# SCH_Just-random_2026-04-02_2.net
KiCad netlist of a schematic drawn in EasyEDA
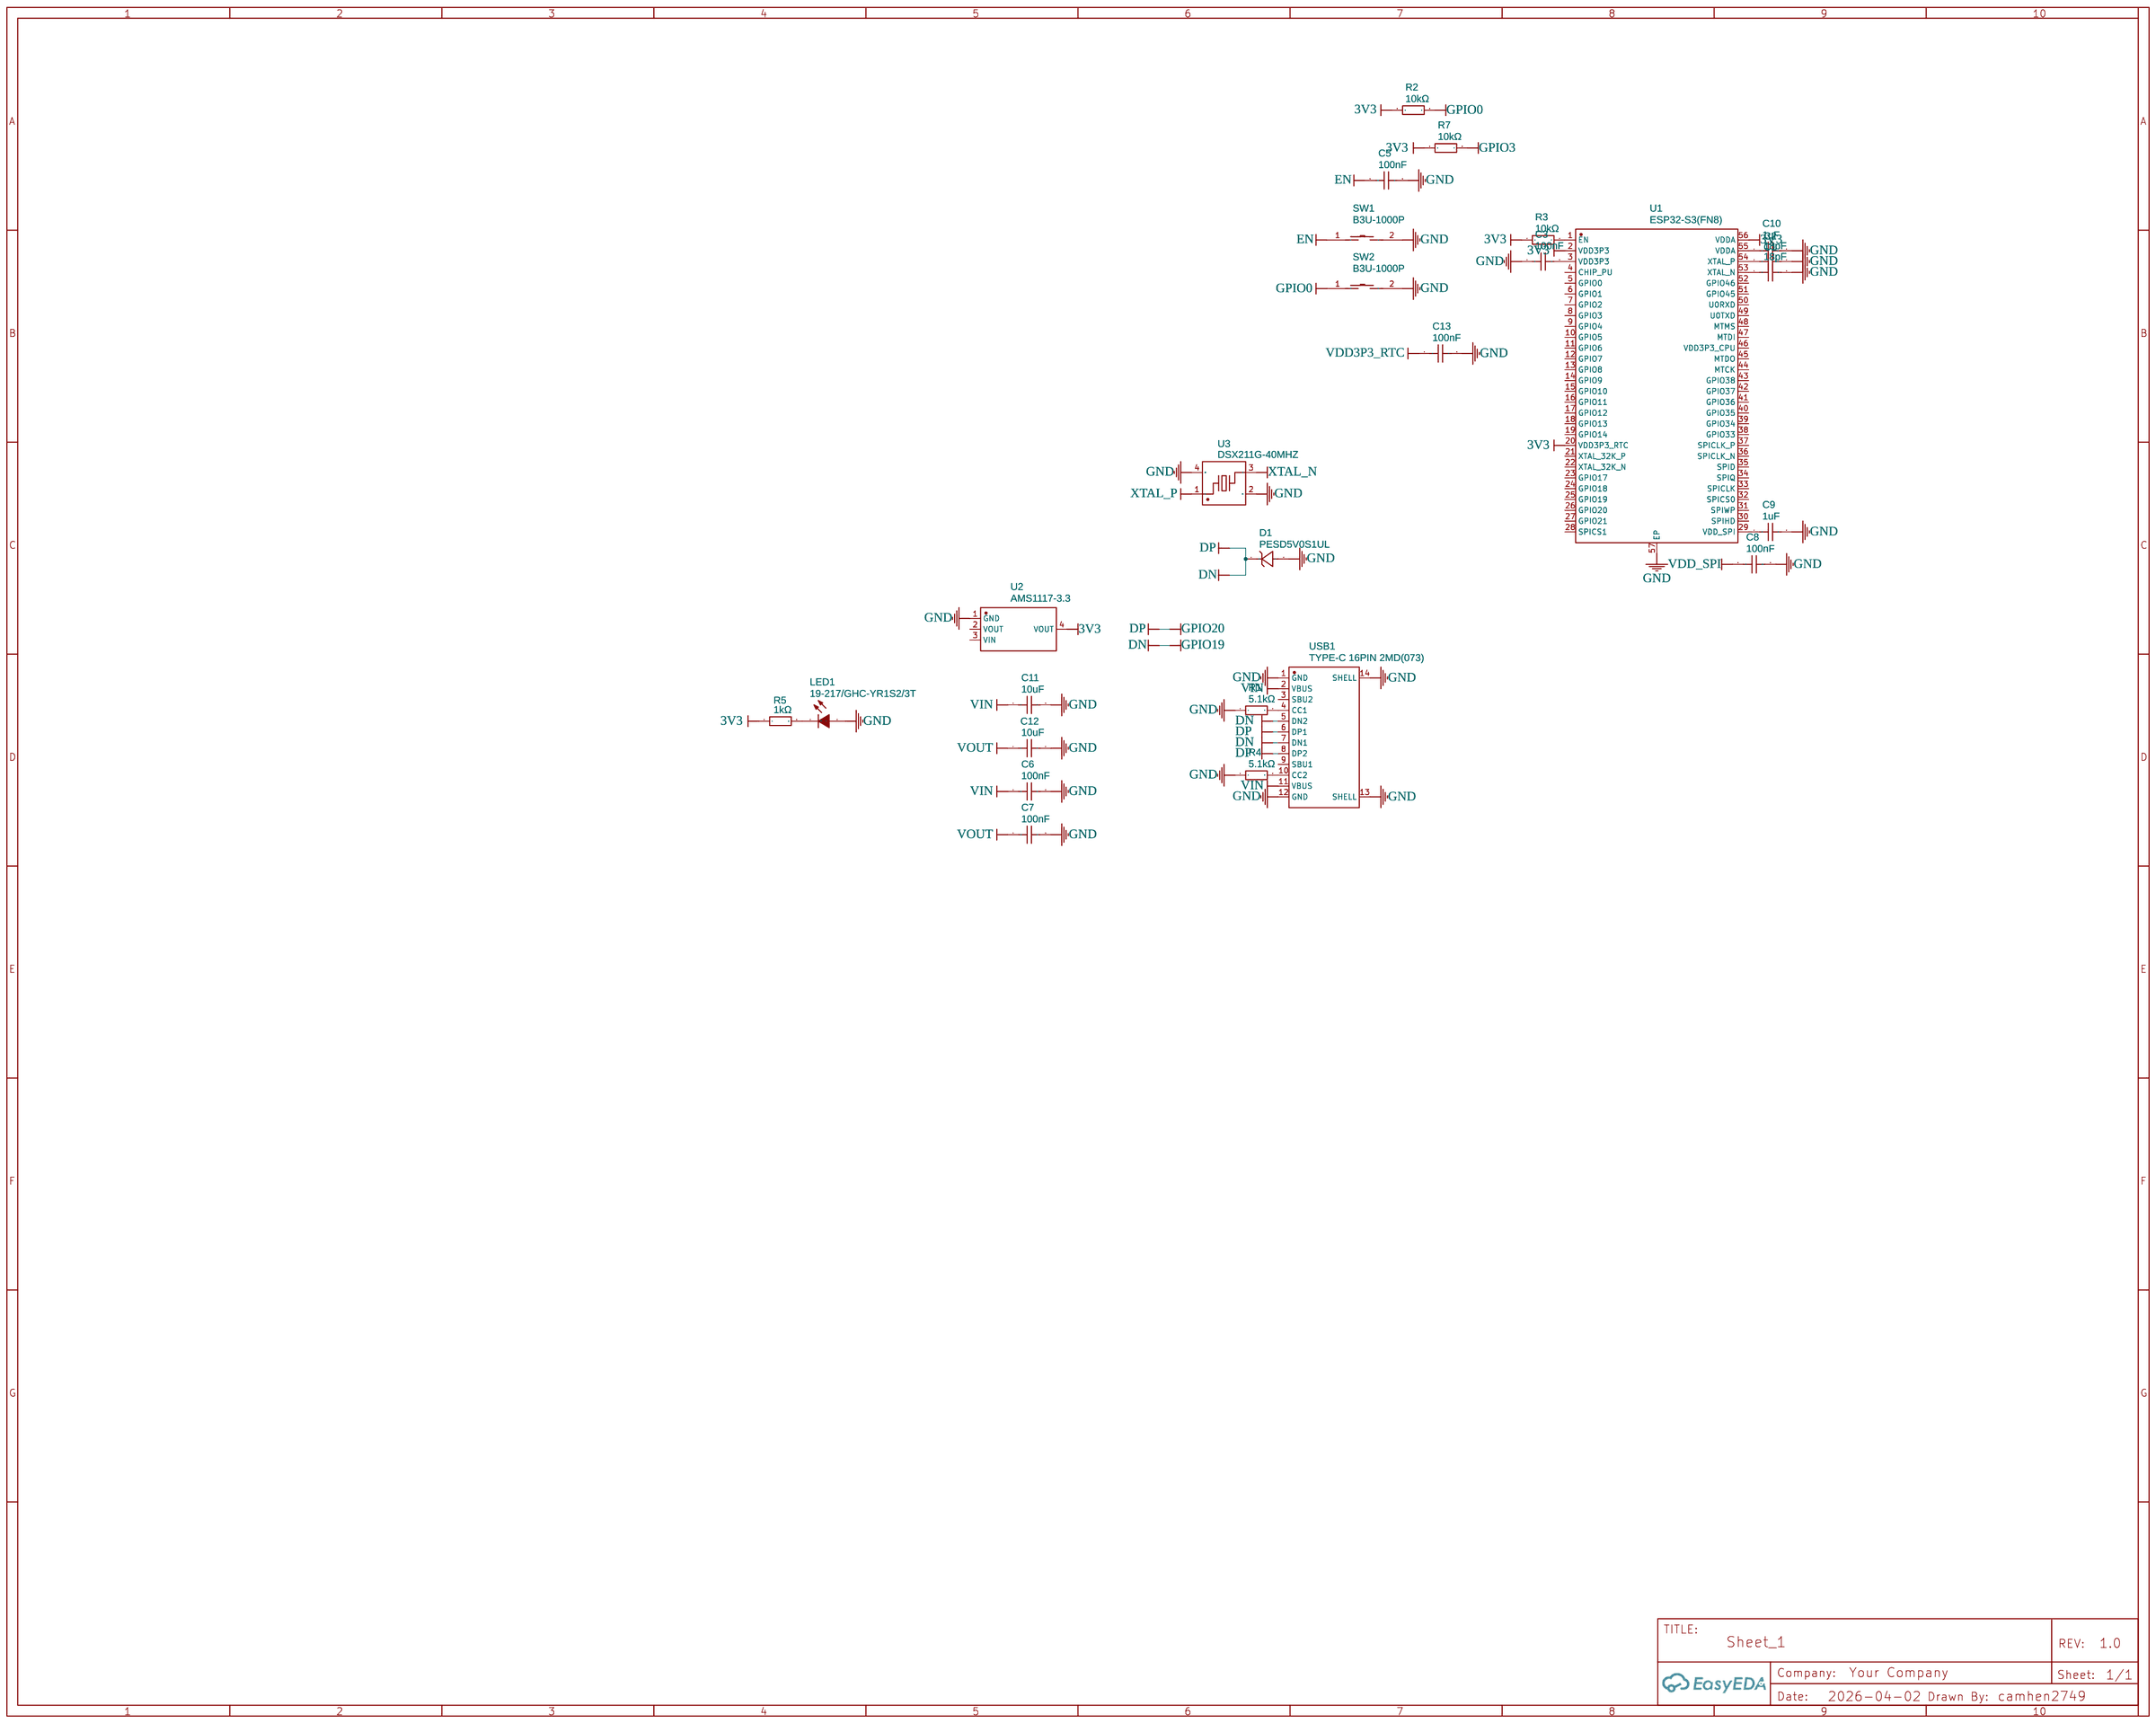
[diagram p0: schematic sheet]

(export (version "E")
  (design (tool "Eeschema 10.0.6"))
  (components
    (comp (ref "C1")
      (value "18pF")
      (fields
        (field (name "Manufacturer Part") "CL05C180JB5NNNC")
        (field (name "Manufacturer") "SAMSUNG(三星)")
      )
      (libsource (lib "") (part "CL05C180JB5NNNC"))
    )
    (comp (ref "C2")
      (value "18pF")
      (fields
        (field (name "Manufacturer Part") "CL05C180JB5NNNC")
        (field (name "Manufacturer") "SAMSUNG(三星)")
      )
      (libsource (lib "") (part "CL05C180JB5NNNC_1"))
    )
    (comp (ref "C3")
      (value "100nF")
      (fields
        (field (name "Manufacturer Part") "CL05B104KO5NNNC")
        (field (name "Manufacturer") "SAMSUNG(三星)")
      )
      (libsource (lib "") (part "CL05B104KO5NNNC"))
    )
    (comp (ref "C5")
      (value "100nF")
      (fields
        (field (name "Manufacturer Part") "CL05B104KO5NNNC")
        (field (name "Manufacturer") "SAMSUNG(三星)")
      )
      (libsource (lib "") (part "CL05B104KO5NNNC"))
    )
    (comp (ref "C6")
      (value "100nF")
      (fields
        (field (name "Manufacturer Part") "CL05B104KO5NNNC")
        (field (name "Manufacturer") "SAMSUNG(三星)")
      )
      (libsource (lib "") (part "CL05B104KO5NNNC"))
    )
    (comp (ref "C7")
      (value "100nF")
      (fields
        (field (name "Manufacturer Part") "CL05B104KO5NNNC")
        (field (name "Manufacturer") "SAMSUNG(三星)")
      )
      (libsource (lib "") (part "CL05B104KO5NNNC"))
    )
    (comp (ref "C8")
      (value "100nF")
      (fields
        (field (name "Manufacturer Part") "CL05B104KO5NNNC")
        (field (name "Manufacturer") "SAMSUNG(三星)")
      )
      (libsource (lib "") (part "CL05B104KO5NNNC"))
    )
    (comp (ref "C9")
      (value "1uF")
      (fields
        (field (name "Manufacturer Part") "CL05A105KA5NQNC")
        (field (name "Manufacturer") "SAMSUNG(三星)")
      )
      (libsource (lib "") (part "CL05A105KA5NQNC"))
    )
    (comp (ref "C10")
      (value "1uF")
      (fields
        (field (name "Manufacturer Part") "CL05A105KA5NQNC")
        (field (name "Manufacturer") "SAMSUNG(三星)")
      )
      (libsource (lib "") (part "CL05A105KA5NQNC"))
    )
    (comp (ref "C11")
      (value "10uF")
      (fields
        (field (name "Manufacturer Part") "CL21A106KAYNNNE")
        (field (name "Manufacturer") "SAMSUNG(三星)")
      )
      (libsource (lib "") (part "CL21A106KAYNNNE"))
    )
    (comp (ref "C12")
      (value "10uF")
      (fields
        (field (name "Manufacturer Part") "CL21A106KAYNNNE")
        (field (name "Manufacturer") "SAMSUNG(三星)")
      )
      (libsource (lib "") (part "CL21A106KAYNNNE"))
    )
    (comp (ref "C13")
      (value "100nF")
      (fields
        (field (name "Manufacturer Part") "CL05B104KO5NNNC")
        (field (name "Manufacturer") "SAMSUNG(三星)")
      )
      (libsource (lib "") (part "CL05B104KO5NNNC"))
    )
    (comp (ref "D1")
      (value "PESD5V0S1UL")
      (fields (field (name "Manufacturer") "TECH PUBLIC(台舟)"))
      (libsource (lib "") (part "PESD5V0S1UL"))
    )
    (comp (ref "LED1")
      (value "19-217/GHC-YR1S2/3T")
      (fields (field (name "Manufacturer") "EVERLIGHT(亿光)"))
      (libsource (lib "") (part "19-217/GHC-YR1S2/3T"))
    )
    (comp (ref "R1")
      (value "5.1kΩ")
      (fields (field (name "Manufacturer Part") "RC0402FR-075K1L") (field (name "Manufacturer") "YAGEO(国巨)"))
      (libsource (lib "") (part "RC0402FR-075K1L"))
    )
    (comp (ref "R2")
      (value "10kΩ")
      (fields (field (name "Manufacturer Part") "RC0402FR-0710KL") (field (name "Manufacturer") "YAGEO(国巨)"))
      (libsource (lib "") (part "RC0402FR-0710KL"))
    )
    (comp (ref "R3")
      (value "10kΩ")
      (fields (field (name "Manufacturer Part") "RC0402FR-0710KL") (field (name "Manufacturer") "YAGEO(国巨)"))
      (libsource (lib "") (part "RC0402FR-0710KL"))
    )
    (comp (ref "R4")
      (value "5.1kΩ")
      (fields (field (name "Manufacturer Part") "RC0402FR-075K1L") (field (name "Manufacturer") "YAGEO(国巨)"))
      (libsource (lib "") (part "RC0402FR-075K1L"))
    )
    (comp (ref "R5")
      (value "1kΩ")
      (fields (field (name "Manufacturer Part") "RC0402FR-071KL") (field (name "Manufacturer") "YAGEO(国巨)"))
      (libsource (lib "") (part "RC0402FR-071KL"))
    )
    (comp (ref "R7")
      (value "10kΩ")
      (fields (field (name "Manufacturer Part") "RC0402FR-0710KL") (field (name "Manufacturer") "YAGEO(国巨)"))
      (libsource (lib "") (part "RC0402FR-0710KL"))
    )
    (comp (ref "SW1")
      (value "B3U-1000P")
      (fields (field (name "Manufacturer") "OMRON(欧姆龙)"))
      (libsource (lib "") (part "B3U-1000P"))
    )
    (comp (ref "SW2")
      (value "B3U-1000P")
      (fields (field (name "Manufacturer") "OMRON(欧姆龙)"))
      (libsource (lib "") (part "B3U-1000P"))
    )
    (comp (ref "U1")
      (value "ESP32-S3(FN8)")
      (fields (field (name "Manufacturer Part") "ESP32-S3FN8") (field (name "Manufacturer") "ESPRESSIF(乐鑫)"))
      (libsource (lib "") (part "ESP32-S3(FN8)"))
    )
    (comp (ref "U2")
      (value "AMS1117-3.3")
      (fields (field (name "Manufacturer") "AMS"))
      (libsource (lib "") (part "AMS1117-3.3"))
    )
    (comp (ref "U3")
      (value "DSX211G-40MHZ")
      (fields (field (name "Manufacturer Part") "DSX211G-40MHz"))
      (libsource (lib "") (part "DSX211G-40MHZ"))
    )
    (comp (ref "USB1")
      (value "TYPE-C 16PIN 2MD(073)")
      (fields (field (name "Manufacturer") "SHOU HAN(首韩)"))
      (libsource (lib "") (part "TYPE-C 16PIN 2MD(073)"))
    )
  )
  (nets
    (net (code "1") (name "3V3") (class "Default")
      (node (ref "R2") (pin "1") (pinfunction "1_1") (pintype "input"))
      (node (ref "R3") (pin "1") (pinfunction "1_1") (pintype "input"))
      (node (ref "R5") (pin "1") (pinfunction "1_1") (pintype "input"))
      (node (ref "R7") (pin "1") (pinfunction "1_1") (pintype "input"))
      (node (ref "U1") (pin "2") (pinfunction "VDD3P3_2") (pintype "unspecified"))
      (node (ref "U1") (pin "20") (pinfunction "VDD3P3_RTC_20") (pintype "unspecified"))
      (node (ref "U1") (pin "56") (pinfunction "VDDA_56") (pintype "unspecified"))
      (node (ref "U2") (pin "4") (pinfunction "VOUT_4") (pintype "unspecified"))
    )
    (net (code "2") (name "DN") (class "Default")
      (node (ref "D1") (pin "1") (pinfunction "C_1") (pintype "unspecified"))
      (node (ref "USB1") (pin "5") (pinfunction "DN2_5") (pintype "unspecified"))
      (node (ref "USB1") (pin "6") (pinfunction "DP1_6") (pintype "unspecified"))
      (node (ref "USB1") (pin "7") (pinfunction "DN1_7") (pintype "unspecified"))
      (node (ref "USB1") (pin "8") (pinfunction "DP2_8") (pintype "unspecified"))
    )
    (net (code "3") (name "EN") (class "Default")
      (node (ref "C5") (pin "1") (pinfunction "1_1") (pintype "unspecified"))
      (node (ref "SW1") (pin "1") (pinfunction "1_1") (pintype "unspecified"))
    )
    (net (code "4") (name "GND") (class "Default")
      (node (ref "C1") (pin "2") (pinfunction "2_2") (pintype "unspecified"))
      (node (ref "C10") (pin "2") (pinfunction "2_2") (pintype "unspecified"))
      (node (ref "C11") (pin "2") (pinfunction "2_2") (pintype "unspecified"))
      (node (ref "C12") (pin "2") (pinfunction "2_2") (pintype "unspecified"))
      (node (ref "C13") (pin "2") (pinfunction "2_2") (pintype "unspecified"))
      (node (ref "C2") (pin "1") (pinfunction "1_1") (pintype "unspecified"))
      (node (ref "C3") (pin "1") (pinfunction "1_1") (pintype "unspecified"))
      (node (ref "C5") (pin "2") (pinfunction "2_2") (pintype "unspecified"))
      (node (ref "C6") (pin "2") (pinfunction "2_2") (pintype "unspecified"))
      (node (ref "C7") (pin "2") (pinfunction "2_2") (pintype "unspecified"))
      (node (ref "C8") (pin "2") (pinfunction "2_2") (pintype "unspecified"))
      (node (ref "C9") (pin "2") (pinfunction "2_2") (pintype "unspecified"))
      (node (ref "D1") (pin "2") (pinfunction "A_2") (pintype "unspecified"))
      (node (ref "LED1") (pin "2") (pinfunction "A_2") (pintype "input"))
      (node (ref "R1") (pin "1") (pinfunction "1_1") (pintype "input"))
      (node (ref "R4") (pin "1") (pinfunction "1_1") (pintype "input"))
      (node (ref "SW1") (pin "2") (pinfunction "2_2") (pintype "unspecified"))
      (node (ref "SW2") (pin "2") (pinfunction "2_2") (pintype "unspecified"))
      (node (ref "U1") (pin "57") (pinfunction "EP_57") (pintype "unspecified"))
      (node (ref "U2") (pin "1") (pinfunction "GND_1") (pintype "unspecified"))
      (node (ref "U3") (pin "2") (pinfunction "GND/NC_2") (pintype "input"))
      (node (ref "U3") (pin "4") (pinfunction "GND/NC_4") (pintype "input"))
      (node (ref "USB1") (pin "1") (pinfunction "GND_1") (pintype "unspecified"))
      (node (ref "USB1") (pin "12") (pinfunction "GND_12") (pintype "unspecified"))
      (node (ref "USB1") (pin "13") (pinfunction "SHELL_13") (pintype "unspecified"))
      (node (ref "USB1") (pin "14") (pinfunction "SHELL_14") (pintype "unspecified"))
    )
    (net (code "5") (name "GPIO0") (class "Default")
      (node (ref "R2") (pin "2") (pinfunction "2_2") (pintype "input"))
      (node (ref "SW2") (pin "1") (pinfunction "1_1") (pintype "unspecified"))
    )
    (net (code "6") (name "GPIO3") (class "Default")
      (node (ref "R7") (pin "2") (pinfunction "2_2") (pintype "input"))
    )
    (net (code "7") (name "Net-(C3-Pad2)") (class "Default")
      (node (ref "C3") (pin "2") (pinfunction "2_2") (pintype "unspecified"))
      (node (ref "U1") (pin "3") (pinfunction "VDD3P3_3") (pintype "unspecified"))
    )
    (net (code "8") (name "Net-(C10-Pad1)") (class "Default")
      (node (ref "C10") (pin "1") (pinfunction "1_1") (pintype "unspecified"))
      (node (ref "U1") (pin "55") (pinfunction "VDDA_55") (pintype "unspecified"))
    )
    (net (code "9") (name "Net-(LED1-C)") (class "Default")
      (node (ref "LED1") (pin "1") (pinfunction "C_1") (pintype "input"))
      (node (ref "R5") (pin "2") (pinfunction "2_2") (pintype "input"))
    )
    (net (code "10") (name "Net-(U1-EN)") (class "Default")
      (node (ref "R3") (pin "2") (pinfunction "2_2") (pintype "input"))
      (node (ref "U1") (pin "1") (pinfunction "EN_1") (pintype "unspecified"))
    )
    (net (code "11") (name "Net-(U1-VDD_SPI)") (class "Default")
      (node (ref "C9") (pin "1") (pinfunction "1_1") (pintype "unspecified"))
      (node (ref "U1") (pin "29") (pinfunction "VDD_SPI_29") (pintype "unspecified"))
    )
    (net (code "12") (name "Net-(U1-XTAL_N)") (class "Default")
      (node (ref "C1") (pin "1") (pinfunction "1_1") (pintype "unspecified"))
      (node (ref "U1") (pin "53") (pinfunction "XTAL_N_53") (pintype "unspecified"))
    )
    (net (code "13") (name "Net-(U1-XTAL_P)") (class "Default")
      (node (ref "C2") (pin "2") (pinfunction "2_2") (pintype "unspecified"))
      (node (ref "U1") (pin "54") (pinfunction "XTAL_P_54") (pintype "unspecified"))
    )
    (net (code "14") (name "Net-(USB1-CC1)") (class "Default")
      (node (ref "R1") (pin "2") (pinfunction "2_2") (pintype "input"))
      (node (ref "USB1") (pin "4") (pinfunction "CC1_4") (pintype "unspecified"))
    )
    (net (code "15") (name "Net-(USB1-CC2)") (class "Default")
      (node (ref "R4") (pin "2") (pinfunction "2_2") (pintype "input"))
      (node (ref "USB1") (pin "10") (pinfunction "CC2_10") (pintype "unspecified"))
    )
    (net (code "16") (name "VDD3P3_RTC") (class "Default")
      (node (ref "C13") (pin "1") (pinfunction "1_1") (pintype "unspecified"))
    )
    (net (code "17") (name "VDD_SPI") (class "Default")
      (node (ref "C8") (pin "1") (pinfunction "1_1") (pintype "unspecified"))
    )
    (net (code "18") (name "VIN") (class "Default")
      (node (ref "C11") (pin "1") (pinfunction "1_1") (pintype "unspecified"))
      (node (ref "C6") (pin "1") (pinfunction "1_1") (pintype "unspecified"))
      (node (ref "USB1") (pin "11") (pinfunction "VBUS_11") (pintype "unspecified"))
      (node (ref "USB1") (pin "2") (pinfunction "VBUS_2") (pintype "unspecified"))
    )
    (net (code "19") (name "VOUT") (class "Default")
      (node (ref "C12") (pin "1") (pinfunction "1_1") (pintype "unspecified"))
      (node (ref "C7") (pin "1") (pinfunction "1_1") (pintype "unspecified"))
    )
    (net (code "20") (name "XTAL_N") (class "Default")
      (node (ref "U3") (pin "3") (pinfunction "3_3") (pintype "input"))
    )
    (net (code "21") (name "XTAL_P") (class "Default")
      (node (ref "U3") (pin "1") (pinfunction "1_1") (pintype "input"))
    )
    (net (code "22") (name "unconnected-(U1-CHIP_PU-Pad4)") (class "Default")
      (node (ref "U1") (pin "4") (pinfunction "CHIP_PU_4") (pintype "unspecified"))
    )
    (net (code "23") (name "unconnected-(U1-GPIO0-Pad5)") (class "Default")
      (node (ref "U1") (pin "5") (pinfunction "GPIO0_5") (pintype "unspecified"))
    )
    (net (code "24") (name "unconnected-(U1-GPIO1-Pad6)") (class "Default")
      (node (ref "U1") (pin "6") (pinfunction "GPIO1_6") (pintype "unspecified"))
    )
    (net (code "25") (name "unconnected-(U1-GPIO2-Pad7)") (class "Default")
      (node (ref "U1") (pin "7") (pinfunction "GPIO2_7") (pintype "unspecified"))
    )
    (net (code "26") (name "unconnected-(U1-GPIO3-Pad8)") (class "Default")
      (node (ref "U1") (pin "8") (pinfunction "GPIO3_8") (pintype "unspecified"))
    )
    (net (code "27") (name "unconnected-(U1-GPIO4-Pad9)") (class "Default")
      (node (ref "U1") (pin "9") (pinfunction "GPIO4_9") (pintype "unspecified"))
    )
    (net (code "28") (name "unconnected-(U1-GPIO5-Pad10)") (class "Default")
      (node (ref "U1") (pin "10") (pinfunction "GPIO5_10") (pintype "unspecified"))
    )
    (net (code "29") (name "unconnected-(U1-GPIO6-Pad11)") (class "Default")
      (node (ref "U1") (pin "11") (pinfunction "GPIO6_11") (pintype "unspecified"))
    )
    (net (code "30") (name "unconnected-(U1-GPIO7-Pad12)") (class "Default")
      (node (ref "U1") (pin "12") (pinfunction "GPIO7_12") (pintype "unspecified"))
    )
    (net (code "31") (name "unconnected-(U1-GPIO8-Pad13)") (class "Default")
      (node (ref "U1") (pin "13") (pinfunction "GPIO8_13") (pintype "unspecified"))
    )
    (net (code "32") (name "unconnected-(U1-GPIO9-Pad14)") (class "Default")
      (node (ref "U1") (pin "14") (pinfunction "GPIO9_14") (pintype "unspecified"))
    )
    (net (code "33") (name "unconnected-(U1-GPIO10-Pad15)") (class "Default")
      (node (ref "U1") (pin "15") (pinfunction "GPIO10_15") (pintype "unspecified"))
    )
    (net (code "34") (name "unconnected-(U1-GPIO11-Pad16)") (class "Default")
      (node (ref "U1") (pin "16") (pinfunction "GPIO11_16") (pintype "unspecified"))
    )
    (net (code "35") (name "unconnected-(U1-GPIO12-Pad17)") (class "Default")
      (node (ref "U1") (pin "17") (pinfunction "GPIO12_17") (pintype "unspecified"))
    )
    (net (code "36") (name "unconnected-(U1-GPIO13-Pad18)") (class "Default")
      (node (ref "U1") (pin "18") (pinfunction "GPIO13_18") (pintype "unspecified"))
    )
    (net (code "37") (name "unconnected-(U1-GPIO14-Pad19)") (class "Default")
      (node (ref "U1") (pin "19") (pinfunction "GPIO14_19") (pintype "unspecified"))
    )
    (net (code "38") (name "unconnected-(U1-GPIO17-Pad23)") (class "Default")
      (node (ref "U1") (pin "23") (pinfunction "GPIO17_23") (pintype "unspecified"))
    )
    (net (code "39") (name "unconnected-(U1-GPIO18-Pad24)") (class "Default")
      (node (ref "U1") (pin "24") (pinfunction "GPIO18_24") (pintype "unspecified"))
    )
    (net (code "40") (name "unconnected-(U1-GPIO19-Pad25)") (class "Default")
      (node (ref "U1") (pin "25") (pinfunction "GPIO19_25") (pintype "unspecified"))
    )
    (net (code "41") (name "unconnected-(U1-GPIO20-Pad26)") (class "Default")
      (node (ref "U1") (pin "26") (pinfunction "GPIO20_26") (pintype "unspecified"))
    )
    (net (code "42") (name "unconnected-(U1-GPIO21-Pad27)") (class "Default")
      (node (ref "U1") (pin "27") (pinfunction "GPIO21_27") (pintype "unspecified"))
    )
    (net (code "43") (name "unconnected-(U1-GPIO33-Pad38)") (class "Default")
      (node (ref "U1") (pin "38") (pinfunction "GPIO33_38") (pintype "unspecified"))
    )
    (net (code "44") (name "unconnected-(U1-GPIO34-Pad39)") (class "Default")
      (node (ref "U1") (pin "39") (pinfunction "GPIO34_39") (pintype "unspecified"))
    )
    (net (code "45") (name "unconnected-(U1-GPIO35-Pad40)") (class "Default")
      (node (ref "U1") (pin "40") (pinfunction "GPIO35_40") (pintype "unspecified"))
    )
    (net (code "46") (name "unconnected-(U1-GPIO36-Pad41)") (class "Default")
      (node (ref "U1") (pin "41") (pinfunction "GPIO36_41") (pintype "unspecified"))
    )
    (net (code "47") (name "unconnected-(U1-GPIO37-Pad42)") (class "Default")
      (node (ref "U1") (pin "42") (pinfunction "GPIO37_42") (pintype "unspecified"))
    )
    (net (code "48") (name "unconnected-(U1-GPIO38-Pad43)") (class "Default")
      (node (ref "U1") (pin "43") (pinfunction "GPIO38_43") (pintype "unspecified"))
    )
    (net (code "49") (name "unconnected-(U1-GPIO45-Pad51)") (class "Default")
      (node (ref "U1") (pin "51") (pinfunction "GPIO45_51") (pintype "unspecified"))
    )
    (net (code "50") (name "unconnected-(U1-GPIO46-Pad52)") (class "Default")
      (node (ref "U1") (pin "52") (pinfunction "GPIO46_52") (pintype "unspecified"))
    )
    (net (code "51") (name "unconnected-(U1-MTCK-Pad44)") (class "Default")
      (node (ref "U1") (pin "44") (pinfunction "MTCK_44") (pintype "unspecified"))
    )
    (net (code "52") (name "unconnected-(U1-MTDI-Pad47)") (class "Default")
      (node (ref "U1") (pin "47") (pinfunction "MTDI_47") (pintype "unspecified"))
    )
    (net (code "53") (name "unconnected-(U1-MTDO-Pad45)") (class "Default")
      (node (ref "U1") (pin "45") (pinfunction "MTDO_45") (pintype "unspecified"))
    )
    (net (code "54") (name "unconnected-(U1-MTMS-Pad48)") (class "Default")
      (node (ref "U1") (pin "48") (pinfunction "MTMS_48") (pintype "unspecified"))
    )
    (net (code "55") (name "unconnected-(U1-SPICLK-Pad33)") (class "Default")
      (node (ref "U1") (pin "33") (pinfunction "SPICLK_33") (pintype "unspecified"))
    )
    (net (code "56") (name "unconnected-(U1-SPICLK_N-Pad36)") (class "Default")
      (node (ref "U1") (pin "36") (pinfunction "SPICLK_N_36") (pintype "unspecified"))
    )
    (net (code "57") (name "unconnected-(U1-SPICLK_P-Pad37)") (class "Default")
      (node (ref "U1") (pin "37") (pinfunction "SPICLK_P_37") (pintype "unspecified"))
    )
    (net (code "58") (name "unconnected-(U1-SPICS0-Pad32)") (class "Default")
      (node (ref "U1") (pin "32") (pinfunction "SPICS0_32") (pintype "unspecified"))
    )
    (net (code "59") (name "unconnected-(U1-SPICS1-Pad28)") (class "Default")
      (node (ref "U1") (pin "28") (pinfunction "SPICS1_28") (pintype "unspecified"))
    )
    (net (code "60") (name "unconnected-(U1-SPID-Pad35)") (class "Default")
      (node (ref "U1") (pin "35") (pinfunction "SPID_35") (pintype "unspecified"))
    )
    (net (code "61") (name "unconnected-(U1-SPIHD-Pad30)") (class "Default")
      (node (ref "U1") (pin "30") (pinfunction "SPIHD_30") (pintype "unspecified"))
    )
    (net (code "62") (name "unconnected-(U1-SPIQ-Pad34)") (class "Default")
      (node (ref "U1") (pin "34") (pinfunction "SPIQ_34") (pintype "unspecified"))
    )
    (net (code "63") (name "unconnected-(U1-SPIWP-Pad31)") (class "Default")
      (node (ref "U1") (pin "31") (pinfunction "SPIWP_31") (pintype "unspecified"))
    )
    (net (code "64") (name "unconnected-(U1-U0RXD-Pad50)") (class "Default")
      (node (ref "U1") (pin "50") (pinfunction "U0RXD_50") (pintype "unspecified"))
    )
    (net (code "65") (name "unconnected-(U1-U0TXD-Pad49)") (class "Default")
      (node (ref "U1") (pin "49") (pinfunction "U0TXD_49") (pintype "unspecified"))
    )
    (net (code "66") (name "unconnected-(U1-VDD3P3_CPU-Pad46)") (class "Default")
      (node (ref "U1") (pin "46") (pinfunction "VDD3P3_CPU_46") (pintype "unspecified"))
    )
    (net (code "67") (name "unconnected-(U1-XTAL_32K_N-Pad22)") (class "Default")
      (node (ref "U1") (pin "22") (pinfunction "XTAL_32K_N_22") (pintype "unspecified"))
    )
    (net (code "68") (name "unconnected-(U1-XTAL_32K_P-Pad21)") (class "Default")
      (node (ref "U1") (pin "21") (pinfunction "XTAL_32K_P_21") (pintype "unspecified"))
    )
    (net (code "69") (name "unconnected-(U2-VIN-Pad3)") (class "Default")
      (node (ref "U2") (pin "3") (pinfunction "VIN_3") (pintype "unspecified"))
    )
    (net (code "70") (name "unconnected-(U2-VOUT-Pad2)") (class "Default")
      (node (ref "U2") (pin "2") (pinfunction "VOUT_2") (pintype "unspecified"))
    )
    (net (code "71") (name "unconnected-(USB1-SBU1-Pad9)") (class "Default")
      (node (ref "USB1") (pin "9") (pinfunction "SBU1_9") (pintype "unspecified"))
    )
    (net (code "72") (name "unconnected-(USB1-SBU2-Pad3)") (class "Default")
      (node (ref "USB1") (pin "3") (pinfunction "SBU2_3") (pintype "unspecified"))
    )
  )
)
